# sche.net
KiCad netlist of a schematic drawn in EasyEDA
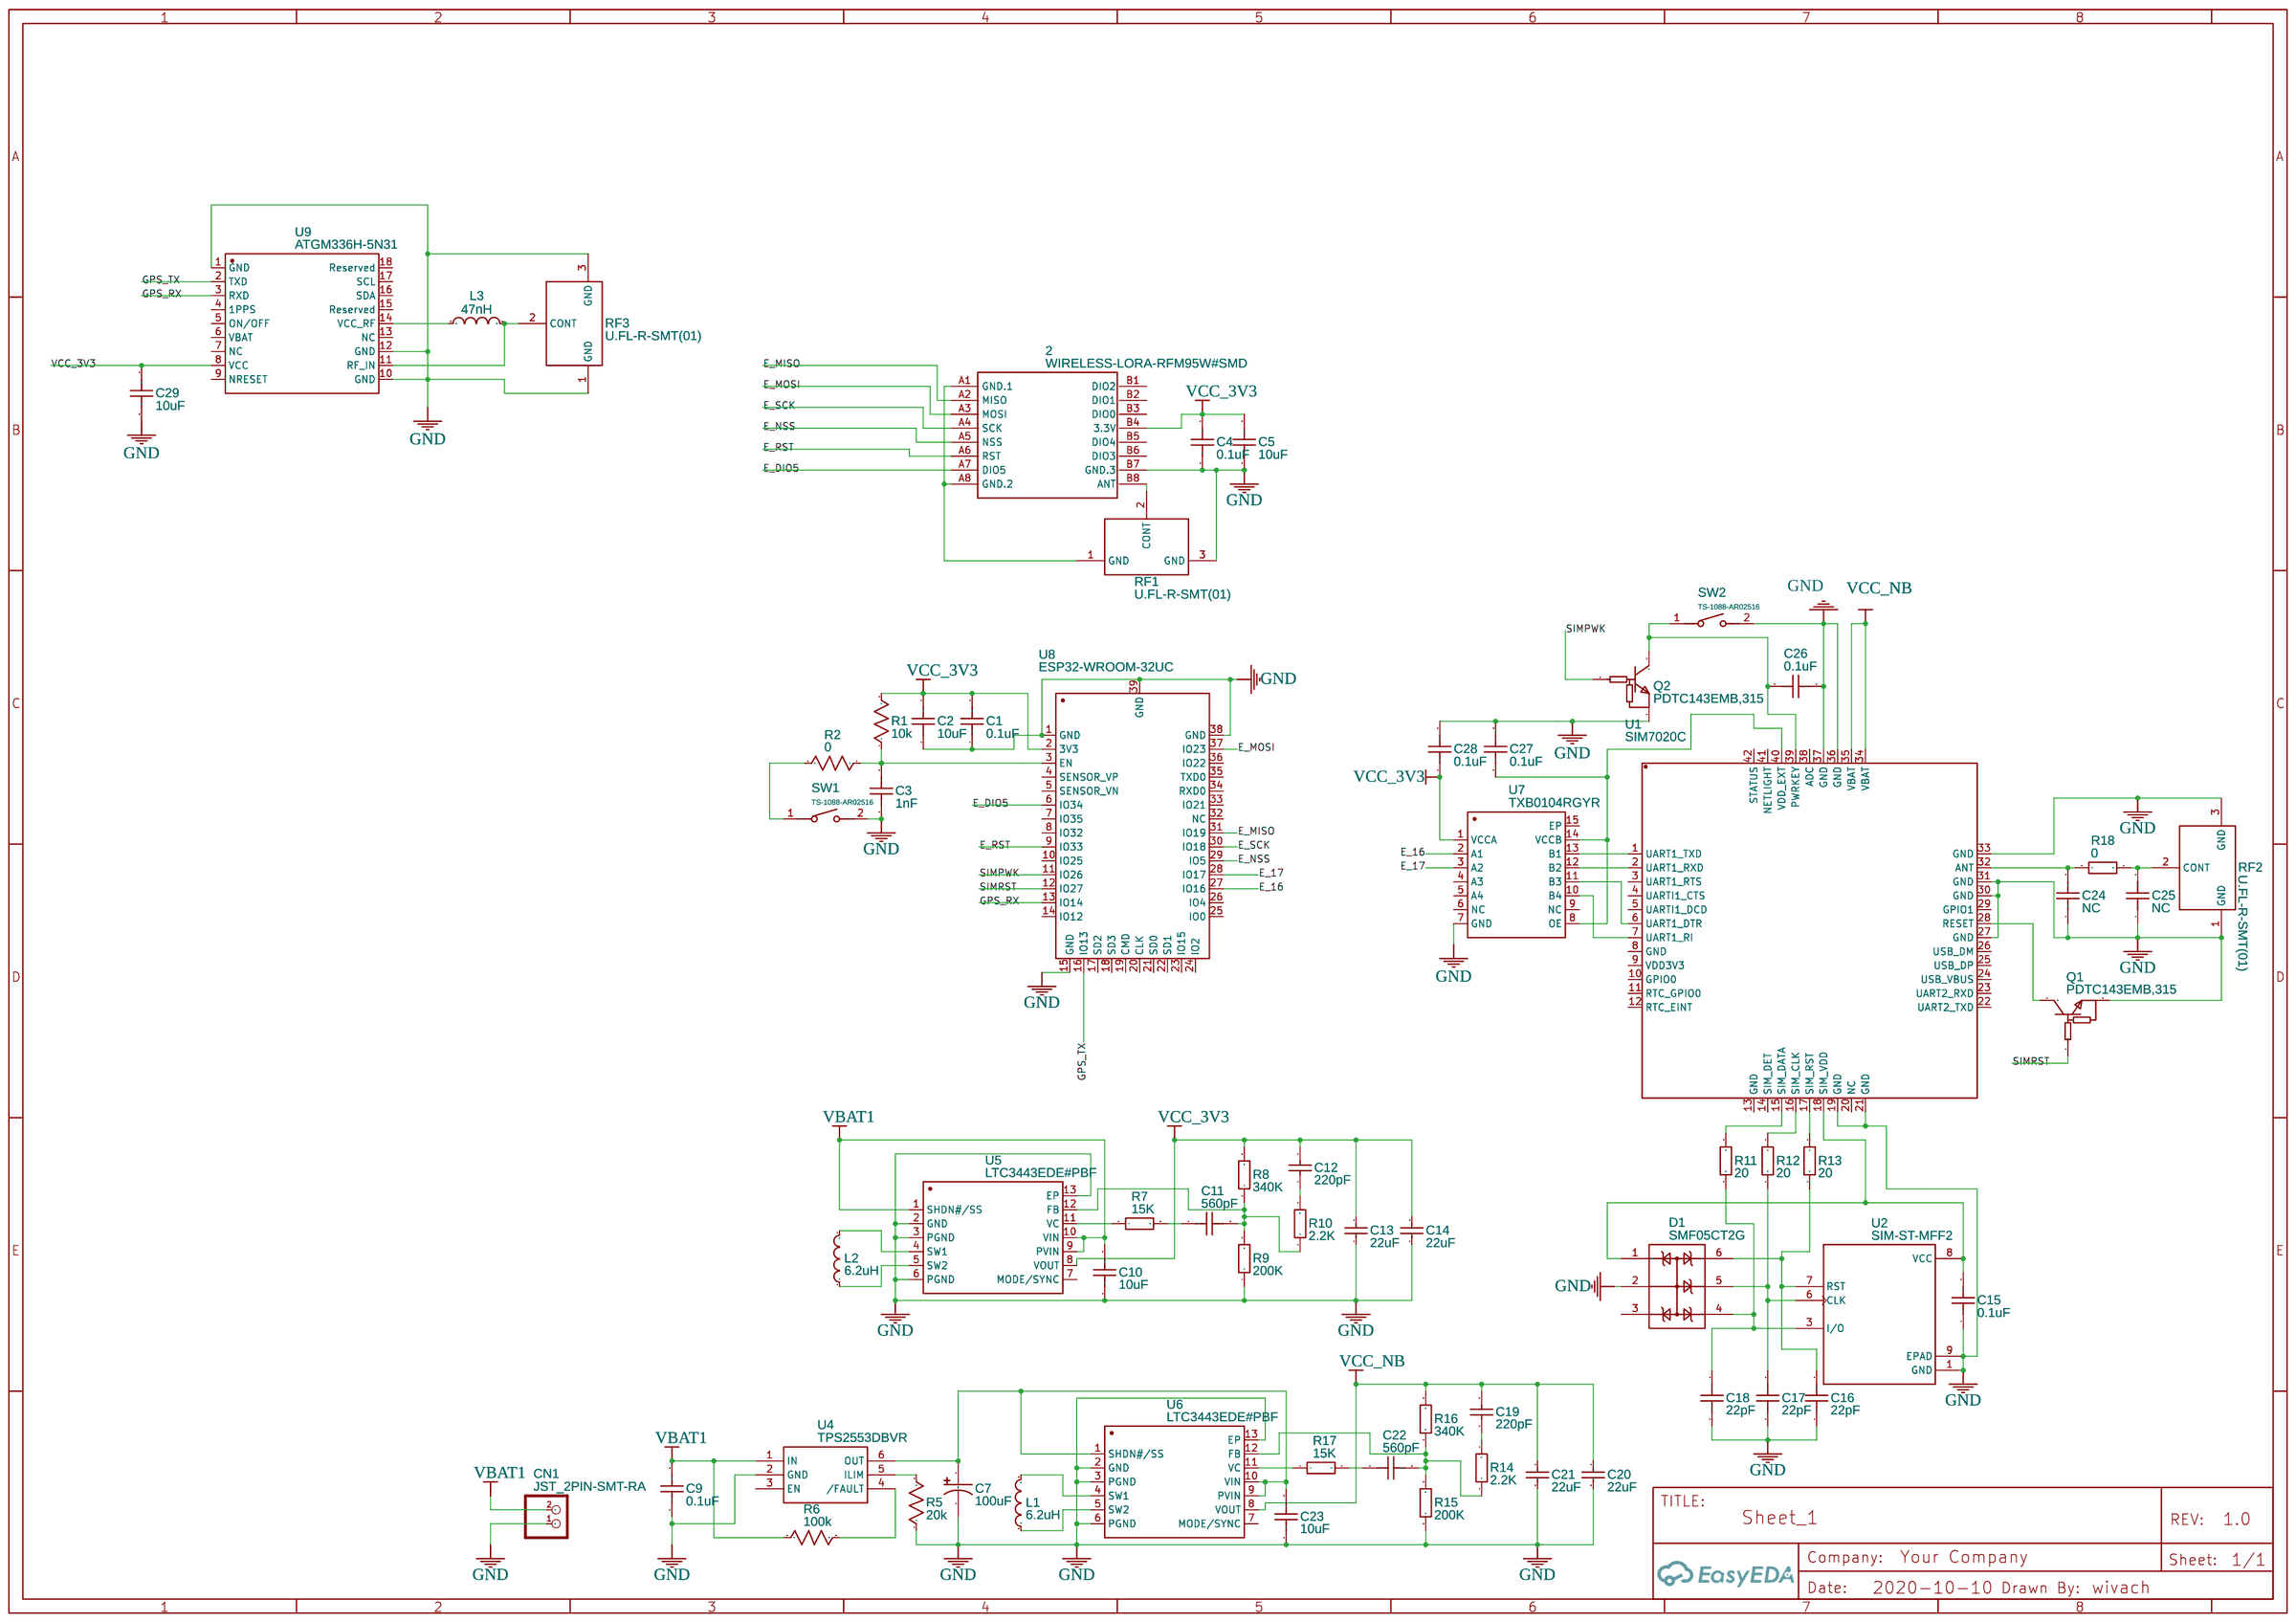
[diagram p0: schematic sheet]

(export (version "E")
  (design (tool "Eeschema 10.0.6"))
  (components
    (comp (ref "2") (value "WIRELESS-LORA-RFM95W#SMD") (libsource (lib "") (part "WIRELESS-LORA-RFM95W#SMD")))
    (comp (ref "C1")
      (value "0.1uF")
      (fields
        (field (name "BOM_Manufacturer Part") "GRM188R71H104KA93D")
        (field (name "BOM_Supplier Part") "C77055")
      )
      (libsource (lib "") (part "C_0603_US"))
    )
    (comp (ref "C2")
      (value "10uF")
      (fields
        (field (name "BOM_Manufacturer Part") "GRM188R60J106ME47D")
        (field (name "BOM_Supplier Part") "C77041")
      )
      (libsource (lib "") (part "C_0603_US"))
    )
    (comp (ref "C3")
      (value "1nF")
      (fields
        (field (name "BOM_Manufacturer Part") "TCC0603X7R102K500CT")
        (field (name "BOM_Supplier Part") "C282515")
      )
      (libsource (lib "") (part "C_0603_US"))
    )
    (comp (ref "C4")
      (value "0.1uF")
      (fields
        (field (name "BOM_Manufacturer Part") "GRM188R71H104KA93D")
        (field (name "BOM_Supplier Part") "C77055")
      )
      (libsource (lib "") (part "C_0603_US"))
    )
    (comp (ref "C5")
      (value "10uF")
      (fields
        (field (name "BOM_Manufacturer Part") "GRM188R60J106ME47D")
        (field (name "BOM_Supplier Part") "C77041")
      )
      (libsource (lib "") (part "C_0603_US"))
    )
    (comp (ref "C7")
      (value "100uF")
      (fields
        (field (name "BOM_Manufacturer Part") "TC212B107M010Y")
        (field (name "BOM_Supplier Part") "C110782")
      )
      (libsource (lib "") (part "TC212B107M010Y"))
    )
    (comp (ref "C9")
      (value "0.1uF")
      (fields
        (field (name "BOM_Manufacturer Part") "GRM188R71H104KA93D")
        (field (name "BOM_Supplier Part") "C77055")
      )
      (libsource (lib "") (part "C_0603_US"))
    )
    (comp (ref "C10")
      (value "10uF")
      (fields
        (field (name "BOM_Manufacturer Part") "C0805X5R106K160NT")
        (field (name "BOM_Supplier Part") "C466793")
      )
      (libsource (lib "") (part "C0805X5R106K160NT"))
    )
    (comp (ref "C11")
      (value "560pF")
      (fields
        (field (name "BOM_Manufacturer Part") "0603CG561J500NT")
        (field (name "BOM_Supplier Part") "C43962")
      )
      (libsource (lib "") (part "0603CG561J500NT"))
    )
    (comp (ref "C12")
      (value "220pF")
      (fields
        (field (name "BOM_Manufacturer Part") "CL10B221KB8NNNC")
        (field (name "BOM_Supplier Part") "C1603")
      )
      (libsource (lib "") (part "CL10B221KB8NNNC"))
    )
    (comp (ref "C13")
      (value "22uF")
      (fields
        (field (name "BOM_Manufacturer Part") "JMK316ABJ226KL-T")
        (field (name "BOM_Supplier Part") "C478848")
      )
      (libsource (lib "") (part "JMK316ABJ226KL-T"))
    )
    (comp (ref "C14")
      (value "22uF")
      (fields
        (field (name "BOM_Manufacturer Part") "JMK316ABJ226KL-T")
        (field (name "BOM_Supplier Part") "C478848")
      )
      (libsource (lib "") (part "JMK316ABJ226KL-T"))
    )
    (comp (ref "C15")
      (value "0.1uF")
      (fields
        (field (name "BOM_Manufacturer Part") "GRM188R71H104KA93D")
        (field (name "BOM_Supplier Part") "C77055")
      )
      (libsource (lib "") (part "C_0603_US"))
    )
    (comp (ref "C16")
      (value "22pF")
      (fields
        (field (name "BOM_Manufacturer Part") "CC0603GRNPO9BN220")
        (field (name "BOM_Supplier Part") "C327276")
      )
      (libsource (lib "") (part "CC0603GRNPO9BN220"))
    )
    (comp (ref "C17")
      (value "22pF")
      (fields
        (field (name "BOM_Manufacturer Part") "CC0603GRNPO9BN220")
        (field (name "BOM_Supplier Part") "C327276")
      )
      (libsource (lib "") (part "CC0603GRNPO9BN220"))
    )
    (comp (ref "C18")
      (value "22pF")
      (fields
        (field (name "BOM_Manufacturer Part") "CC0603GRNPO9BN220")
        (field (name "BOM_Supplier Part") "C327276")
      )
      (libsource (lib "") (part "CC0603GRNPO9BN220"))
    )
    (comp (ref "C19")
      (value "220pF")
      (fields
        (field (name "BOM_Manufacturer Part") "CL10B221KB8NNNC")
        (field (name "BOM_Supplier Part") "C1603")
      )
      (libsource (lib "") (part "CL10B221KB8NNNC"))
    )
    (comp (ref "C20")
      (value "22uF")
      (fields
        (field (name "BOM_Manufacturer Part") "JMK316ABJ226KL-T")
        (field (name "BOM_Supplier Part") "C478848")
      )
      (libsource (lib "") (part "JMK316ABJ226KL-T"))
    )
    (comp (ref "C21")
      (value "22uF")
      (fields
        (field (name "BOM_Manufacturer Part") "JMK316ABJ226KL-T")
        (field (name "BOM_Supplier Part") "C478848")
      )
      (libsource (lib "") (part "JMK316ABJ226KL-T"))
    )
    (comp (ref "C22")
      (value "560pF")
      (fields
        (field (name "BOM_Manufacturer Part") "0603CG561J500NT")
        (field (name "BOM_Supplier Part") "C43962")
      )
      (libsource (lib "") (part "0603CG561J500NT"))
    )
    (comp (ref "C23")
      (value "10uF")
      (fields
        (field (name "BOM_Manufacturer Part") "C0805X5R106K160NT")
        (field (name "BOM_Supplier Part") "C466793")
      )
      (libsource (lib "") (part "C0805X5R106K160NT"))
    )
    (comp (ref "C24") (value "NC") (libsource (lib "") (part "C_0603_US")))
    (comp (ref "C25") (value "NC") (libsource (lib "") (part "C_0603_US")))
    (comp (ref "C26")
      (value "0.1uF")
      (fields
        (field (name "BOM_Manufacturer Part") "GRM188R71H104KA93D")
        (field (name "BOM_Supplier Part") "C77055")
      )
      (libsource (lib "") (part "C_0603_US_1"))
    )
    (comp (ref "C27")
      (value "0.1uF")
      (fields
        (field (name "BOM_Manufacturer Part") "GRM188R71H104KA93D")
        (field (name "BOM_Supplier Part") "C77055")
      )
      (libsource (lib "") (part "C_0603_US"))
    )
    (comp (ref "C28")
      (value "0.1uF")
      (fields
        (field (name "BOM_Manufacturer Part") "GRM188R71H104KA93D")
        (field (name "BOM_Supplier Part") "C77055")
      )
      (libsource (lib "") (part "C_0603_US"))
    )
    (comp (ref "C29")
      (value "10uF")
      (fields
        (field (name "BOM_Manufacturer Part") "GRM188R60J106ME47D")
        (field (name "BOM_Supplier Part") "C77041")
      )
      (libsource (lib "") (part "C_0603_US"))
    )
    (comp (ref "CN1")
      (value "JST_2PIN-SMT-RA")
      (fields
        (field (name "BOM_Manufacturer Part") "S2B-PH-SM4-TB(LF)(SN)")
        (field (name "BOM_Supplier Part") "C295747")
      )
      (libsource (lib "") (part "JST_2PIN-SMT-RA"))
    )
    (comp (ref "D1")
      (value "SMF05CT2G")
      (fields (field (name "BOM_Supplier Part") "C513065"))
      (libsource (lib "") (part "SMF05CT2G"))
    )
    (comp (ref "L1")
      (value "6.2uH")
      (fields
        (field (name "BOM_Manufacturer Part") "CDRH5D28NP-6R2NC")
        (field (name "BOM_Supplier Part") "C312979")
      )
      (libsource (lib "") (part "CDRH5D28NP-6R2NC"))
    )
    (comp (ref "L2")
      (value "6.2uH")
      (fields
        (field (name "BOM_Manufacturer Part") "CDRH5D28NP-6R2NC")
        (field (name "BOM_Supplier Part") "C312979")
      )
      (libsource (lib "") (part "CDRH5D28NP-6R2NC_2"))
    )
    (comp (ref "L3")
      (value "47nH")
      (fields
        (field (name "BOM_Manufacturer Part") "CDRH5D28NP-6R2NC")
        (field (name "BOM_Supplier Part") "C312979")
      )
      (libsource (lib "") (part "CDRH5D28NP-6R2NC_1"))
    )
    (comp (ref "Q1")
      (value "PDTC143EMB,315")
      (fields (field (name "BOM_Supplier Part") "C552203"))
      (libsource (lib "") (part "PDTC143EMB,315_1"))
    )
    (comp (ref "Q2")
      (value "PDTC143EMB,315")
      (fields (field (name "BOM_Supplier Part") "C552203"))
      (libsource (lib "") (part "PDTC143EMB,315"))
    )
    (comp (ref "R1")
      (value "10k")
      (fields
        (field (name "BOM_Manufacturer Part") "RCT0310KJLF")
        (field (name "BOM_Supplier Part") "C177337")
      )
      (libsource (lib "") (part "R_0603_US"))
    )
    (comp (ref "R2")
      (value "0")
      (fields
        (field (name "BOM_Manufacturer Part") "0603WAF0000T5E")
        (field (name "BOM_Supplier Part") "C21189")
      )
      (libsource (lib "") (part "R_0603_US_1"))
    )
    (comp (ref "R5")
      (value "20k")
      (fields
        (field (name "BOM_Manufacturer Part") "SR06X203JTL")
        (field (name "BOM_Supplier Part") "C305157")
      )
      (libsource (lib "") (part "R_0603_US"))
    )
    (comp (ref "R6")
      (value "100k")
      (fields
        (field (name "BOM_Manufacturer Part") "RC0201JR-07100KL")
        (field (name "BOM_Supplier Part") "C106230")
      )
      (libsource (lib "") (part "R_0603_US_2"))
    )
    (comp (ref "R7")
      (value "15K")
      (fields
        (field (name "BOM_Manufacturer Part") "ETCR0603F15K0K9")
        (field (name "BOM_Supplier Part") "C365386")
      )
      (libsource (lib "") (part "ETCR0603F15K0K9"))
    )
    (comp (ref "R8")
      (value "340K")
      (fields
        (field (name "BOM_Manufacturer Part") "AC0603FR-07340KL")
        (field (name "BOM_Supplier Part") "C227826")
      )
      (libsource (lib "") (part "AC0603FR-07340KL"))
    )
    (comp (ref "R9")
      (value "200K")
      (fields
        (field (name "BOM_Manufacturer Part") "AF0603FR-07200KL")
        (field (name "BOM_Supplier Part") "C144091")
      )
      (libsource (lib "") (part "AF0603FR-07200KL"))
    )
    (comp (ref "R10")
      (value "2.2K")
      (fields
        (field (name "BOM_Manufacturer Part") "RMC06032.2K5%N")
        (field (name "BOM_Supplier Part") "C325643")
      )
      (libsource (lib "") (part "RMC06032.2K5%N"))
    )
    (comp (ref "R11")
      (value "20")
      (fields
        (field (name "BOM_Manufacturer Part") "ERJUP3F20R0V")
        (field (name "BOM_Supplier Part") "C544033")
      )
      (libsource (lib "") (part "ERJUP3F20R0V"))
    )
    (comp (ref "R12")
      (value "20")
      (fields
        (field (name "BOM_Manufacturer Part") "ERJUP3F20R0V")
        (field (name "BOM_Supplier Part") "C544033")
      )
      (libsource (lib "") (part "ERJUP3F20R0V"))
    )
    (comp (ref "R13")
      (value "20")
      (fields
        (field (name "BOM_Manufacturer Part") "ERJUP3F20R0V")
        (field (name "BOM_Supplier Part") "C544033")
      )
      (libsource (lib "") (part "ERJUP3F20R0V"))
    )
    (comp (ref "R14")
      (value "2.2K")
      (fields
        (field (name "BOM_Manufacturer Part") "RMC06032.2K5%N")
        (field (name "BOM_Supplier Part") "C325643")
      )
      (libsource (lib "") (part "RMC06032.2K5%N"))
    )
    (comp (ref "R15")
      (value "200K")
      (fields
        (field (name "BOM_Manufacturer Part") "AF0603FR-07200KL")
        (field (name "BOM_Supplier Part") "C144091")
      )
      (libsource (lib "") (part "AF0603FR-07200KL"))
    )
    (comp (ref "R16")
      (value "340K")
      (fields
        (field (name "BOM_Manufacturer Part") "AC0603FR-07340KL")
        (field (name "BOM_Supplier Part") "C227826")
      )
      (libsource (lib "") (part "AC0603FR-07340KL"))
    )
    (comp (ref "R17")
      (value "15K")
      (fields
        (field (name "BOM_Manufacturer Part") "ETCR0603F15K0K9")
        (field (name "BOM_Supplier Part") "C365386")
      )
      (libsource (lib "") (part "ETCR0603F15K0K9"))
    )
    (comp (ref "R18")
      (value "0")
      (fields
        (field (name "BOM_Manufacturer Part") "ERJUP3F20R0V")
        (field (name "BOM_Supplier Part") "C544033")
      )
      (libsource (lib "") (part "ERJUP3F20R0V_1"))
    )
    (comp (ref "RF1")
      (value "U.FL-R-SMT(01)")
      (fields (field (name "BOM_Supplier Part") "C434812"))
      (libsource (lib "") (part "U.FL-R-SMT(01)_1"))
    )
    (comp (ref "RF2")
      (value "U.FL-R-SMT(01)")
      (fields (field (name "BOM_Supplier Part") "C434812"))
      (libsource (lib "") (part "U.FL-R-SMT(01)"))
    )
    (comp (ref "RF3")
      (value "U.FL-R-SMT(01)")
      (fields (field (name "BOM_Supplier Part") "C434812"))
      (libsource (lib "") (part "U.FL-R-SMT(01)"))
    )
    (comp (ref "SW1")
      (value "TS-1088-AR02516")
      (fields (field (name "BOM_Supplier Part") "C720478"))
      (libsource (lib "") (part "TS-1088-AR02516"))
    )
    (comp (ref "SW2")
      (value "TS-1088-AR02516")
      (fields (field (name "BOM_Supplier Part") "C720478"))
      (libsource (lib "") (part "TS-1088-AR02516"))
    )
    (comp (ref "U1")
      (value "SIM7020C")
      (fields (field (name "BOM_Supplier Part") "C188351"))
      (libsource (lib "") (part "SIM7020C"))
    )
    (comp (ref "U2") (value "SIM-ST-MFF2") (libsource (lib "") (part "SIM-ST-MFF2")))
    (comp (ref "U4")
      (value "TPS2553DBVR")
      (fields (field (name "BOM_Supplier Part") "C55266"))
      (libsource (lib "") (part "TPS2553DBVR"))
    )
    (comp (ref "U5")
      (value "LTC3443EDE#PBF")
      (fields (field (name "BOM_Supplier Part") "C684784"))
      (libsource (lib "") (part "LTC3443EDE#PBF"))
    )
    (comp (ref "U6")
      (value "LTC3443EDE#PBF")
      (fields (field (name "BOM_Supplier Part") "C684784"))
      (libsource (lib "") (part "LTC3443EDE#PBF"))
    )
    (comp (ref "U7")
      (value "TXB0104RGYR")
      (fields (field (name "BOM_Supplier Part") "C400708"))
      (libsource (lib "") (part "TXB0104RGYR"))
    )
    (comp (ref "U8")
      (value "ESP32-WROOM-32UC")
      (fields (field (name "BOM_Supplier Part") "C473014"))
      (libsource (lib "") (part "ESP32-WROOM-32UC"))
    )
    (comp (ref "U9")
      (value "ATGM336H-5N31")
      (fields (field (name "BOM_Supplier Part") "C90770"))
      (libsource (lib "") (part "ATGM336H-5N31"))
    )
  )
  (nets
    (net (code "1") (name "/E_16") (class "Default")
      (node (ref "U7") (pin "2") (pinfunction "A1_2") (pintype "unspecified"))
      (node (ref "U8") (pin "27") (pinfunction "IO16_27") (pintype "unspecified"))
    )
    (net (code "2") (name "/E_17") (class "Default")
      (node (ref "U7") (pin "3") (pinfunction "A2_3") (pintype "unspecified"))
      (node (ref "U8") (pin "28") (pinfunction "IO17_28") (pintype "unspecified"))
    )
    (net (code "3") (name "/E_DIO5") (class "Default")
      (node (ref "2") (pin "A7") (pinfunction "DIO5_A7") (pintype "bidirectional"))
      (node (ref "U8") (pin "6") (pinfunction "IO34_6") (pintype "unspecified"))
    )
    (net (code "4") (name "/E_MISO") (class "Default")
      (node (ref "2") (pin "A2") (pinfunction "MISO_A2") (pintype "bidirectional"))
      (node (ref "U8") (pin "31") (pinfunction "IO19_31") (pintype "unspecified"))
    )
    (net (code "5") (name "/E_MOSI") (class "Default")
      (node (ref "2") (pin "A3") (pinfunction "MOSI_A3") (pintype "bidirectional"))
      (node (ref "U8") (pin "37") (pinfunction "IO23_37") (pintype "unspecified"))
    )
    (net (code "6") (name "/E_NSS") (class "Default")
      (node (ref "2") (pin "A5") (pinfunction "NSS_A5") (pintype "bidirectional"))
      (node (ref "U8") (pin "29") (pinfunction "IO5_29") (pintype "unspecified"))
    )
    (net (code "7") (name "/E_RST") (class "Default")
      (node (ref "2") (pin "A6") (pinfunction "RST_A6") (pintype "bidirectional"))
      (node (ref "U8") (pin "9") (pinfunction "IO33_9") (pintype "unspecified"))
    )
    (net (code "8") (name "/E_SCK") (class "Default")
      (node (ref "2") (pin "A4") (pinfunction "SCK_A4") (pintype "bidirectional"))
      (node (ref "U8") (pin "30") (pinfunction "IO18_30") (pintype "unspecified"))
    )
    (net (code "9") (name "/GPS_RX") (class "Default")
      (node (ref "U8") (pin "13") (pinfunction "IO14_13") (pintype "unspecified"))
      (node (ref "U9") (pin "3") (pinfunction "RXD_3") (pintype "unspecified"))
    )
    (net (code "10") (name "/GPS_TX") (class "Default")
      (node (ref "U8") (pin "16") (pinfunction "IO13_16") (pintype "unspecified"))
      (node (ref "U9") (pin "2") (pinfunction "TXD_2") (pintype "unspecified"))
    )
    (net (code "11") (name "/SIMPWK") (class "Default")
      (node (ref "Q2") (pin "1") (pinfunction "B_1") (pintype "unspecified"))
      (node (ref "U8") (pin "11") (pinfunction "IO26_11") (pintype "unspecified"))
    )
    (net (code "12") (name "/SIMRST") (class "Default")
      (node (ref "Q1") (pin "1") (pinfunction "B_1") (pintype "unspecified"))
      (node (ref "U8") (pin "12") (pinfunction "IO27_12") (pintype "unspecified"))
    )
    (net (code "13") (name "GND") (class "Default")
      (node (ref "2") (pin "B7") (pinfunction "GND.3_B7") (pintype "bidirectional"))
      (node (ref "C1") (pin "1") (pinfunction "1_1") (pintype "unspecified"))
      (node (ref "C10") (pin "1") (pinfunction "1_1") (pintype "unspecified"))
      (node (ref "C13") (pin "1") (pinfunction "1_1") (pintype "input"))
      (node (ref "C14") (pin "1") (pinfunction "1_1") (pintype "input"))
      (node (ref "C15") (pin "1") (pinfunction "1_1") (pintype "unspecified"))
      (node (ref "C16") (pin "1") (pinfunction "1_1") (pintype "unspecified"))
      (node (ref "C17") (pin "1") (pinfunction "1_1") (pintype "unspecified"))
      (node (ref "C18") (pin "1") (pinfunction "1_1") (pintype "unspecified"))
      (node (ref "C2") (pin "1") (pinfunction "1_1") (pintype "unspecified"))
      (node (ref "C20") (pin "1") (pinfunction "1_1") (pintype "input"))
      (node (ref "C21") (pin "1") (pinfunction "1_1") (pintype "input"))
      (node (ref "C23") (pin "1") (pinfunction "1_1") (pintype "unspecified"))
      (node (ref "C24") (pin "1") (pinfunction "1_1") (pintype "unspecified"))
      (node (ref "C25") (pin "1") (pinfunction "1_1") (pintype "unspecified"))
      (node (ref "C26") (pin "1") (pinfunction "1_1") (pintype "unspecified"))
      (node (ref "C27") (pin "2") (pinfunction "2_2") (pintype "unspecified"))
      (node (ref "C28") (pin "2") (pinfunction "2_2") (pintype "unspecified"))
      (node (ref "C29") (pin "1") (pinfunction "1_1") (pintype "unspecified"))
      (node (ref "C3") (pin "1") (pinfunction "1_1") (pintype "unspecified"))
      (node (ref "C4") (pin "1") (pinfunction "1_1") (pintype "unspecified"))
      (node (ref "C5") (pin "1") (pinfunction "1_1") (pintype "unspecified"))
      (node (ref "C7") (pin "2") (pinfunction "2_2") (pintype "unspecified"))
      (node (ref "C9") (pin "1") (pinfunction "1_1") (pintype "unspecified"))
      (node (ref "CN1") (pin "1") (pinfunction "2_1") (pintype "unspecified"))
      (node (ref "D1") (pin "2") (pinfunction "A_2") (pintype "unspecified"))
      (node (ref "Q1") (pin "2") (pinfunction "E_2") (pintype "unspecified"))
      (node (ref "Q2") (pin "2") (pinfunction "E_2") (pintype "unspecified"))
      (node (ref "R15") (pin "1") (pinfunction "1_1") (pintype "unspecified"))
      (node (ref "R5") (pin "1") (pinfunction "1_1") (pintype "unspecified"))
      (node (ref "R9") (pin "1") (pinfunction "1_1") (pintype "unspecified"))
      (node (ref "RF1") (pin "3") (pinfunction "GND_3") (pintype "unspecified"))
      (node (ref "RF2") (pin "1") (pinfunction "GND_1") (pintype "unspecified"))
      (node (ref "RF2") (pin "3") (pinfunction "GND_3") (pintype "unspecified"))
      (node (ref "RF3") (pin "1") (pinfunction "GND_1") (pintype "unspecified"))
      (node (ref "RF3") (pin "3") (pinfunction "GND_3") (pintype "unspecified"))
      (node (ref "SW1") (pin "2") (pinfunction "2_2") (pintype "unspecified"))
      (node (ref "SW2") (pin "2") (pinfunction "2_2") (pintype "unspecified"))
      (node (ref "U1") (pin "19") (pinfunction "GND_19") (pintype "unspecified"))
      (node (ref "U1") (pin "21") (pinfunction "GND_21") (pintype "unspecified"))
      (node (ref "U1") (pin "27") (pinfunction "GND_27") (pintype "unspecified"))
      (node (ref "U1") (pin "30") (pinfunction "GND_30") (pintype "unspecified"))
      (node (ref "U1") (pin "31") (pinfunction "GND_31") (pintype "unspecified"))
      (node (ref "U1") (pin "33") (pinfunction "GND_33") (pintype "unspecified"))
      (node (ref "U1") (pin "36") (pinfunction "GND_36") (pintype "unspecified"))
      (node (ref "U1") (pin "37") (pinfunction "GND_37") (pintype "unspecified"))
      (node (ref "U2") (pin "1") (pinfunction "GND_1") (pintype "bidirectional"))
      (node (ref "U2") (pin "9") (pinfunction "EPAD_9") (pintype "bidirectional"))
      (node (ref "U4") (pin "2") (pinfunction "GND_2") (pintype "unspecified"))
      (node (ref "U5") (pin "13") (pinfunction "EP_13") (pintype "unspecified"))
      (node (ref "U5") (pin "2") (pinfunction "GND_2") (pintype "unspecified"))
      (node (ref "U5") (pin "3") (pinfunction "PGND_3") (pintype "unspecified"))
      (node (ref "U5") (pin "6") (pinfunction "PGND_6") (pintype "unspecified"))
      (node (ref "U6") (pin "13") (pinfunction "EP_13") (pintype "unspecified"))
      (node (ref "U6") (pin "2") (pinfunction "GND_2") (pintype "unspecified"))
      (node (ref "U6") (pin "3") (pinfunction "PGND_3") (pintype "unspecified"))
      (node (ref "U6") (pin "6") (pinfunction "PGND_6") (pintype "unspecified"))
      (node (ref "U7") (pin "7") (pinfunction "GND_7") (pintype "unspecified"))
      (node (ref "U8") (pin "1") (pinfunction "GND_1") (pintype "unspecified"))
      (node (ref "U8") (pin "15") (pinfunction "GND_15") (pintype "unspecified"))
      (node (ref "U8") (pin "38") (pinfunction "GND_38") (pintype "unspecified"))
      (node (ref "U8") (pin "39") (pinfunction "GND_39") (pintype "unspecified"))
      (node (ref "U9") (pin "1") (pinfunction "GND_1") (pintype "unspecified"))
      (node (ref "U9") (pin "10") (pinfunction "GND_10") (pintype "unspecified"))
      (node (ref "U9") (pin "12") (pinfunction "GND_12") (pintype "unspecified"))
    )
    (net (code "14") (name "Net-(2-ANT)") (class "Default")
      (node (ref "2") (pin "B8") (pinfunction "ANT_B8") (pintype "bidirectional"))
      (node (ref "RF1") (pin "2") (pinfunction "CONT_2") (pintype "unspecified"))
    )
    (net (code "15") (name "Net-(2-GND.1)") (class "Default")
      (node (ref "2") (pin "A1") (pinfunction "GND.1_A1") (pintype "bidirectional"))
      (node (ref "2") (pin "A8") (pinfunction "GND.2_A8") (pintype "bidirectional"))
      (node (ref "RF1") (pin "1") (pinfunction "GND_1") (pintype "unspecified"))
    )
    (net (code "16") (name "Net-(C11-Pad1)") (class "Default")
      (node (ref "C11") (pin "1") (pinfunction "1_1") (pintype "unspecified"))
      (node (ref "R7") (pin "2") (pinfunction "2_2") (pintype "unspecified"))
    )
    (net (code "17") (name "Net-(C12-Pad1)") (class "Default")
      (node (ref "C12") (pin "1") (pinfunction "1_1") (pintype "input"))
      (node (ref "R10") (pin "2") (pinfunction "2_2") (pintype "unspecified"))
    )
    (net (code "18") (name "Net-(C19-Pad1)") (class "Default")
      (node (ref "C19") (pin "1") (pinfunction "1_1") (pintype "input"))
      (node (ref "R14") (pin "2") (pinfunction "2_2") (pintype "unspecified"))
    )
    (net (code "19") (name "Net-(C22-Pad1)") (class "Default")
      (node (ref "C22") (pin "1") (pinfunction "1_1") (pintype "unspecified"))
      (node (ref "R17") (pin "2") (pinfunction "2_2") (pintype "unspecified"))
    )
    (net (code "20") (name "Net-(D1-C1)") (class "Default")
      (node (ref "C15") (pin "2") (pinfunction "2_2") (pintype "unspecified"))
      (node (ref "D1") (pin "1") (pinfunction "C1_1") (pintype "unspecified"))
      (node (ref "U1") (pin "18") (pinfunction "SIM_VDD_18") (pintype "unspecified"))
      (node (ref "U2") (pin "8") (pinfunction "VCC_8") (pintype "bidirectional"))
    )
    (net (code "21") (name "Net-(D1-C3)") (class "Default")
      (node (ref "C18") (pin "2") (pinfunction "2_2") (pintype "unspecified"))
      (node (ref "D1") (pin "4") (pinfunction "C3_4") (pintype "unspecified"))
      (node (ref "R11") (pin "1") (pinfunction "1_1") (pintype "unspecified"))
      (node (ref "U2") (pin "3") (pinfunction "I/O_3") (pintype "bidirectional"))
    )
    (net (code "22") (name "Net-(D1-C4)") (class "Default")
      (node (ref "C17") (pin "2") (pinfunction "2_2") (pintype "unspecified"))
      (node (ref "D1") (pin "5") (pinfunction "C4_5") (pintype "unspecified"))
      (node (ref "R12") (pin "1") (pinfunction "1_1") (pintype "unspecified"))
      (node (ref "U2") (pin "6") (pinfunction "CLK_6") (pintype "bidirectional"))
    )
    (net (code "23") (name "Net-(D1-C5)") (class "Default")
      (node (ref "C16") (pin "2") (pinfunction "2_2") (pintype "unspecified"))
      (node (ref "D1") (pin "6") (pinfunction "C5_6") (pintype "unspecified"))
      (node (ref "R13") (pin "1") (pinfunction "1_1") (pintype "unspecified"))
      (node (ref "U2") (pin "7") (pinfunction "RST_7") (pintype "bidirectional"))
    )
    (net (code "24") (name "Net-(Q1-C)") (class "Default")
      (node (ref "Q1") (pin "3") (pinfunction "C_3") (pintype "unspecified"))
      (node (ref "U1") (pin "28") (pinfunction "RESET_28") (pintype "unspecified"))
    )
    (net (code "25") (name "Net-(Q2-C)") (class "Default")
      (node (ref "C26") (pin "2") (pinfunction "2_2") (pintype "unspecified"))
      (node (ref "Q2") (pin "3") (pinfunction "C_3") (pintype "unspecified"))
      (node (ref "SW2") (pin "1") (pinfunction "1_1") (pintype "unspecified"))
      (node (ref "U1") (pin "39") (pinfunction "PWRKEY_39") (pintype "unspecified"))
    )
    (net (code "26") (name "Net-(R2-Pad2)") (class "Default")
      (node (ref "R2") (pin "2") (pinfunction "2_2") (pintype "unspecified"))
      (node (ref "SW1") (pin "1") (pinfunction "1_1") (pintype "unspecified"))
    )
    (net (code "27") (name "Net-(RF2-CONT)") (class "Default")
      (node (ref "C25") (pin "2") (pinfunction "2_2") (pintype "unspecified"))
      (node (ref "R18") (pin "1") (pinfunction "1_1") (pintype "unspecified"))
      (node (ref "RF2") (pin "2") (pinfunction "CONT_2") (pintype "unspecified"))
    )
    (net (code "28") (name "Net-(RF3-CONT)") (class "Default")
      (node (ref "L3") (pin "2") (pinfunction "2_2") (pintype "unspecified"))
      (node (ref "RF3") (pin "2") (pinfunction "CONT_2") (pintype "unspecified"))
      (node (ref "U9") (pin "11") (pinfunction "RF_IN_11") (pintype "unspecified"))
    )
    (net (code "29") (name "Net-(U1-ANT)") (class "Default")
      (node (ref "C24") (pin "2") (pinfunction "2_2") (pintype "unspecified"))
      (node (ref "R18") (pin "2") (pinfunction "2_2") (pintype "unspecified"))
      (node (ref "U1") (pin "32") (pinfunction "ANT_32") (pintype "unspecified"))
    )
    (net (code "30") (name "Net-(U1-SIM_CLK)") (class "Default")
      (node (ref "R12") (pin "2") (pinfunction "2_2") (pintype "unspecified"))
      (node (ref "U1") (pin "16") (pinfunction "SIM_CLK_16") (pintype "unspecified"))
    )
    (net (code "31") (name "Net-(U1-SIM_DATA)") (class "Default")
      (node (ref "R11") (pin "2") (pinfunction "2_2") (pintype "unspecified"))
      (node (ref "U1") (pin "15") (pinfunction "SIM_DATA_15") (pintype "unspecified"))
    )
    (net (code "32") (name "Net-(U1-SIM_RST)") (class "Default")
      (node (ref "R13") (pin "2") (pinfunction "2_2") (pintype "unspecified"))
      (node (ref "U1") (pin "17") (pinfunction "SIM_RST_17") (pintype "unspecified"))
    )
    (net (code "33") (name "Net-(U1-UART1_DTR)") (class "Default")
      (node (ref "U1") (pin "6") (pinfunction "UART1_DTR_6") (pintype "unspecified"))
      (node (ref "U7") (pin "11") (pinfunction "B3_11") (pintype "unspecified"))
    )
    (net (code "34") (name "Net-(U1-UART1_RI)") (class "Default")
      (node (ref "U1") (pin "7") (pinfunction "UART1_RI_7") (pintype "unspecified"))
      (node (ref "U7") (pin "10") (pinfunction "B4_10") (pintype "unspecified"))
    )
    (net (code "35") (name "Net-(U1-UART1_RXD)") (class "Default")
      (node (ref "U1") (pin "2") (pinfunction "UART1_RXD_2") (pintype "unspecified"))
      (node (ref "U7") (pin "12") (pinfunction "B2_12") (pintype "unspecified"))
    )
    (net (code "36") (name "Net-(U1-UART1_TXD)") (class "Default")
      (node (ref "U1") (pin "1") (pinfunction "UART1_TXD_1") (pintype "unspecified"))
      (node (ref "U7") (pin "13") (pinfunction "B1_13") (pintype "unspecified"))
    )
    (net (code "37") (name "Net-(U1-VDD_EXT)") (class "Default")
      (node (ref "C27") (pin "1") (pinfunction "1_1") (pintype "unspecified"))
      (node (ref "U1") (pin "40") (pinfunction "VDD_EXT_40") (pintype "unspecified"))
      (node (ref "U7") (pin "14") (pinfunction "VCCB_14") (pintype "unspecified"))
      (node (ref "U7") (pin "8") (pinfunction "OE_8") (pintype "unspecified"))
    )
    (net (code "38") (name "Net-(U4-ILIM)") (class "Default")
      (node (ref "R5") (pin "2") (pinfunction "2_2") (pintype "unspecified"))
      (node (ref "U4") (pin "5") (pinfunction "ILIM_5") (pintype "unspecified"))
    )
    (net (code "39") (name "Net-(U4-OUT)") (class "Default")
      (node (ref "C23") (pin "2") (pinfunction "2_2") (pintype "unspecified"))
      (node (ref "C7") (pin "1") (pinfunction "1_1") (pintype "unspecified"))
      (node (ref "U4") (pin "6") (pinfunction "OUT_6") (pintype "unspecified"))
      (node (ref "U6") (pin "1") (pinfunction "SHDN#/SS_1") (pintype "unspecified"))
      (node (ref "U6") (pin "10") (pinfunction "VIN_10") (pintype "unspecified"))
      (node (ref "U6") (pin "9") (pinfunction "PVIN_9") (pintype "unspecified"))
    )
    (net (code "40") (name "Net-(U4-{slash}FAULT)") (class "Default")
      (node (ref "R6") (pin "2") (pinfunction "2_2") (pintype "unspecified"))
      (node (ref "U4") (pin "4") (pinfunction "/FAULT_4") (pintype "unspecified"))
    )
    (net (code "41") (name "Net-(U5-FB)") (class "Default")
      (node (ref "C11") (pin "2") (pinfunction "2_2") (pintype "unspecified"))
      (node (ref "R10") (pin "1") (pinfunction "1_1") (pintype "unspecified"))
      (node (ref "R8") (pin "1") (pinfunction "1_1") (pintype "unspecified"))
      (node (ref "R9") (pin "2") (pinfunction "2_2") (pintype "unspecified"))
      (node (ref "U5") (pin "12") (pinfunction "FB_12") (pintype "unspecified"))
    )
    (net (code "42") (name "Net-(U5-SW1)") (class "Default")
      (node (ref "L2") (pin "2") (pinfunction "2_2") (pintype "unspecified"))
      (node (ref "U5") (pin "4") (pinfunction "SW1_4") (pintype "unspecified"))
    )
    (net (code "43") (name "Net-(U5-SW2)") (class "Default")
      (node (ref "L2") (pin "1") (pinfunction "1_1") (pintype "unspecified"))
      (node (ref "U5") (pin "5") (pinfunction "SW2_5") (pintype "unspecified"))
    )
    (net (code "44") (name "Net-(U5-VC)") (class "Default")
      (node (ref "R7") (pin "1") (pinfunction "1_1") (pintype "unspecified"))
      (node (ref "U5") (pin "11") (pinfunction "VC_11") (pintype "unspecified"))
    )
    (net (code "45") (name "Net-(U6-FB)") (class "Default")
      (node (ref "C22") (pin "2") (pinfunction "2_2") (pintype "unspecified"))
      (node (ref "R14") (pin "1") (pinfunction "1_1") (pintype "unspecified"))
      (node (ref "R15") (pin "2") (pinfunction "2_2") (pintype "unspecified"))
      (node (ref "R16") (pin "1") (pinfunction "1_1") (pintype "unspecified"))
      (node (ref "U6") (pin "12") (pinfunction "FB_12") (pintype "unspecified"))
    )
    (net (code "46") (name "Net-(U6-SW1)") (class "Default")
      (node (ref "L1") (pin "2") (pinfunction "2_2") (pintype "unspecified"))
      (node (ref "U6") (pin "4") (pinfunction "SW1_4") (pintype "unspecified"))
    )
    (net (code "47") (name "Net-(U6-SW2)") (class "Default")
      (node (ref "L1") (pin "1") (pinfunction "1_1") (pintype "unspecified"))
      (node (ref "U6") (pin "5") (pinfunction "SW2_5") (pintype "unspecified"))
    )
    (net (code "48") (name "Net-(U6-VC)") (class "Default")
      (node (ref "R17") (pin "1") (pinfunction "1_1") (pintype "unspecified"))
      (node (ref "U6") (pin "11") (pinfunction "VC_11") (pintype "unspecified"))
    )
    (net (code "49") (name "Net-(U8-EN)") (class "Default")
      (node (ref "C3") (pin "2") (pinfunction "2_2") (pintype "unspecified"))
      (node (ref "R1") (pin "1") (pinfunction "1_1") (pintype "unspecified"))
      (node (ref "R2") (pin "1") (pinfunction "1_1") (pintype "unspecified"))
      (node (ref "U8") (pin "3") (pinfunction "EN_3") (pintype "unspecified"))
    )
    (net (code "50") (name "Net-(U9-VCC_RF)") (class "Default")
      (node (ref "L3") (pin "1") (pinfunction "1_1") (pintype "unspecified"))
      (node (ref "U9") (pin "14") (pinfunction "VCC_RF_14") (pintype "unspecified"))
    )
    (net (code "51") (name "VBAT1") (class "Default")
      (node (ref "C10") (pin "2") (pinfunction "2_2") (pintype "unspecified"))
      (node (ref "C9") (pin "2") (pinfunction "2_2") (pintype "unspecified"))
      (node (ref "CN1") (pin "2") (pinfunction "1_2") (pintype "unspecified"))
      (node (ref "R6") (pin "1") (pinfunction "1_1") (pintype "unspecified"))
      (node (ref "U4") (pin "1") (pinfunction "IN_1") (pintype "unspecified"))
      (node (ref "U5") (pin "1") (pinfunction "SHDN#/SS_1") (pintype "unspecified"))
      (node (ref "U5") (pin "10") (pinfunction "VIN_10") (pintype "unspecified"))
      (node (ref "U5") (pin "9") (pinfunction "PVIN_9") (pintype "unspecified"))
    )
    (net (code "52") (name "VCC_3V3") (class "Default")
      (node (ref "2") (pin "B4") (pinfunction "3.3V_B4") (pintype "bidirectional"))
      (node (ref "C1") (pin "2") (pinfunction "2_2") (pintype "unspecified"))
      (node (ref "C12") (pin "2") (pinfunction "2_2") (pintype "input"))
      (node (ref "C13") (pin "2") (pinfunction "2_2") (pintype "input"))
      (node (ref "C14") (pin "2") (pinfunction "2_2") (pintype "input"))
      (node (ref "C2") (pin "2") (pinfunction "2_2") (pintype "unspecified"))
      (node (ref "C28") (pin "1") (pinfunction "1_1") (pintype "unspecified"))
      (node (ref "C29") (pin "2") (pinfunction "2_2") (pintype "unspecified"))
      (node (ref "C4") (pin "2") (pinfunction "2_2") (pintype "unspecified"))
      (node (ref "C5") (pin "2") (pinfunction "2_2") (pintype "unspecified"))
      (node (ref "R1") (pin "2") (pinfunction "2_2") (pintype "unspecified"))
      (node (ref "R8") (pin "2") (pinfunction "2_2") (pintype "unspecified"))
      (node (ref "U5") (pin "8") (pinfunction "VOUT_8") (pintype "unspecified"))
      (node (ref "U7") (pin "1") (pinfunction "VCCA_1") (pintype "unspecified"))
      (node (ref "U8") (pin "2") (pinfunction "3V3_2") (pintype "unspecified"))
      (node (ref "U9") (pin "8") (pinfunction "VCC_8") (pintype "unspecified"))
    )
    (net (code "53") (name "VCC_NB") (class "Default")
      (node (ref "C19") (pin "2") (pinfunction "2_2") (pintype "input"))
      (node (ref "C20") (pin "2") (pinfunction "2_2") (pintype "input"))
      (node (ref "C21") (pin "2") (pinfunction "2_2") (pintype "input"))
      (node (ref "R16") (pin "2") (pinfunction "2_2") (pintype "unspecified"))
      (node (ref "U1") (pin "34") (pinfunction "VBAT_34") (pintype "unspecified"))
      (node (ref "U1") (pin "35") (pinfunction "VBAT_35") (pintype "unspecified"))
      (node (ref "U6") (pin "8") (pinfunction "VOUT_8") (pintype "unspecified"))
    )
    (net (code "54") (name "unconnected-(2-DIO0-PadB3)") (class "Default")
      (node (ref "2") (pin "B3") (pinfunction "DIO0_B3") (pintype "bidirectional"))
    )
    (net (code "55") (name "unconnected-(2-DIO1-PadB2)") (class "Default")
      (node (ref "2") (pin "B2") (pinfunction "DIO1_B2") (pintype "bidirectional"))
    )
    (net (code "56") (name "unconnected-(2-DIO2-PadB1)") (class "Default")
      (node (ref "2") (pin "B1") (pinfunction "DIO2_B1") (pintype "bidirectional"))
    )
    (net (code "57") (name "unconnected-(2-DIO3-PadB6)") (class "Default")
      (node (ref "2") (pin "B6") (pinfunction "DIO3_B6") (pintype "bidirectional"))
    )
    (net (code "58") (name "unconnected-(2-DIO4-PadB5)") (class "Default")
      (node (ref "2") (pin "B5") (pinfunction "DIO4_B5") (pintype "bidirectional"))
    )
    (net (code "59") (name "unconnected-(D1-C2-Pad3)") (class "Default")
      (node (ref "D1") (pin "3") (pinfunction "C2_3") (pintype "unspecified"))
    )
    (net (code "60") (name "unconnected-(U1-ADC-Pad38)") (class "Default")
      (node (ref "U1") (pin "38") (pinfunction "ADC_38") (pintype "unspecified"))
    )
    (net (code "61") (name "unconnected-(U1-GND-Pad8)") (class "Default")
      (node (ref "U1") (pin "8") (pinfunction "GND_8") (pintype "unspecified"))
    )
    (net (code "62") (name "unconnected-(U1-GND-Pad13)") (class "Default")
      (node (ref "U1") (pin "13") (pinfunction "GND_13") (pintype "unspecified"))
    )
    (net (code "63") (name "unconnected-(U1-GPIO0-Pad10)") (class "Default")
      (node (ref "U1") (pin "10") (pinfunction "GPIO0_10") (pintype "unspecified"))
    )
    (net (code "64") (name "unconnected-(U1-GPIO1-Pad29)") (class "Default")
      (node (ref "U1") (pin "29") (pinfunction "GPIO1_29") (pintype "unspecified"))
    )
    (net (code "65") (name "unconnected-(U1-NC-Pad20)") (class "Default")
      (node (ref "U1") (pin "20") (pinfunction "NC_20") (pintype "unspecified"))
    )
    (net (code "66") (name "unconnected-(U1-NETLIGHT-Pad41)") (class "Default")
      (node (ref "U1") (pin "41") (pinfunction "NETLIGHT_41") (pintype "unspecified"))
    )
    (net (code "67") (name "unconnected-(U1-RTC_EINT-Pad12)") (class "Default")
      (node (ref "U1") (pin "12") (pinfunction "RTC_EINT_12") (pintype "unspecified"))
    )
    (net (code "68") (name "unconnected-(U1-RTC_GPIO0-Pad11)") (class "Default")
      (node (ref "U1") (pin "11") (pinfunction "RTC_GPIO0_11") (pintype "unspecified"))
    )
    (net (code "69") (name "unconnected-(U1-SIM_DET-Pad14)") (class "Default")
      (node (ref "U1") (pin "14") (pinfunction "SIM_DET_14") (pintype "unspecified"))
    )
    (net (code "70") (name "unconnected-(U1-STATUS-Pad42)") (class "Default")
      (node (ref "U1") (pin "42") (pinfunction "STATUS_42") (pintype "unspecified"))
    )
    (net (code "71") (name "unconnected-(U1-UART1_RTS-Pad3)") (class "Default")
      (node (ref "U1") (pin "3") (pinfunction "UART1_RTS_3") (pintype "unspecified"))
    )
    (net (code "72") (name "unconnected-(U1-UART2_RXD-Pad23)") (class "Default")
      (node (ref "U1") (pin "23") (pinfunction "UART2_RXD_23") (pintype "unspecified"))
    )
    (net (code "73") (name "unconnected-(U1-UART2_TXD-Pad22)") (class "Default")
      (node (ref "U1") (pin "22") (pinfunction "UART2_TXD_22") (pintype "unspecified"))
    )
    (net (code "74") (name "unconnected-(U1-UARTI1_CTS-Pad4)") (class "Default")
      (node (ref "U1") (pin "4") (pinfunction "UARTI1_CTS_4") (pintype "unspecified"))
    )
    (net (code "75") (name "unconnected-(U1-UARTI1_DCD-Pad5)") (class "Default")
      (node (ref "U1") (pin "5") (pinfunction "UARTI1_DCD_5") (pintype "unspecified"))
    )
    (net (code "76") (name "unconnected-(U1-USB_DM-Pad26)") (class "Default")
      (node (ref "U1") (pin "26") (pinfunction "USB_DM_26") (pintype "unspecified"))
    )
    (net (code "77") (name "unconnected-(U1-USB_DP-Pad25)") (class "Default")
      (node (ref "U1") (pin "25") (pinfunction "USB_DP_25") (pintype "unspecified"))
    )
    (net (code "78") (name "unconnected-(U1-USB_VBUS-Pad24)") (class "Default")
      (node (ref "U1") (pin "24") (pinfunction "USB_VBUS_24") (pintype "unspecified"))
    )
    (net (code "79") (name "unconnected-(U1-VDD3V3-Pad9)") (class "Default")
      (node (ref "U1") (pin "9") (pinfunction "VDD3V3_9") (pintype "unspecified"))
    )
    (net (code "80") (name "unconnected-(U4-EN-Pad3)") (class "Default")
      (node (ref "U4") (pin "3") (pinfunction "EN_3") (pintype "unspecified"))
    )
    (net (code "81") (name "unconnected-(U5-MODE{slash}SYNC-Pad7)") (class "Default")
      (node (ref "U5") (pin "7") (pinfunction "MODE/SYNC_7") (pintype "unspecified"))
    )
    (net (code "82") (name "unconnected-(U6-MODE{slash}SYNC-Pad7)") (class "Default")
      (node (ref "U6") (pin "7") (pinfunction "MODE/SYNC_7") (pintype "unspecified"))
    )
    (net (code "83") (name "unconnected-(U7-A3-Pad4)") (class "Default")
      (node (ref "U7") (pin "4") (pinfunction "A3_4") (pintype "unspecified"))
    )
    (net (code "84") (name "unconnected-(U7-A4-Pad5)") (class "Default")
      (node (ref "U7") (pin "5") (pinfunction "A4_5") (pintype "unspecified"))
    )
    (net (code "85") (name "unconnected-(U7-EP-Pad15)") (class "Default")
      (node (ref "U7") (pin "15") (pinfunction "EP_15") (pintype "unspecified"))
    )
    (net (code "86") (name "unconnected-(U7-NC-Pad6)") (class "Default")
      (node (ref "U7") (pin "6") (pinfunction "NC_6") (pintype "unspecified"))
    )
    (net (code "87") (name "unconnected-(U7-NC-Pad9)") (class "Default")
      (node (ref "U7") (pin "9") (pinfunction "NC_9") (pintype "unspecified"))
    )
    (net (code "88") (name "unconnected-(U8-CLK-Pad20)") (class "Default")
      (node (ref "U8") (pin "20") (pinfunction "CLK_20") (pintype "unspecified"))
    )
    (net (code "89") (name "unconnected-(U8-CMD-Pad19)") (class "Default")
      (node (ref "U8") (pin "19") (pinfunction "CMD_19") (pintype "unspecified"))
    )
    (net (code "90") (name "unconnected-(U8-IO0-Pad25)") (class "Default")
      (node (ref "U8") (pin "25") (pinfunction "IO0_25") (pintype "unspecified"))
    )
    (net (code "91") (name "unconnected-(U8-IO2-Pad24)") (class "Default")
      (node (ref "U8") (pin "24") (pinfunction "IO2_24") (pintype "unspecified"))
    )
    (net (code "92") (name "unconnected-(U8-IO4-Pad26)") (class "Default")
      (node (ref "U8") (pin "26") (pinfunction "IO4_26") (pintype "unspecified"))
    )
    (net (code "93") (name "unconnected-(U8-IO12-Pad14)") (class "Default")
      (node (ref "U8") (pin "14") (pinfunction "IO12_14") (pintype "unspecified"))
    )
    (net (code "94") (name "unconnected-(U8-IO15-Pad23)") (class "Default")
      (node (ref "U8") (pin "23") (pinfunction "IO15_23") (pintype "unspecified"))
    )
    (net (code "95") (name "unconnected-(U8-IO21-Pad33)") (class "Default")
      (node (ref "U8") (pin "33") (pinfunction "IO21_33") (pintype "unspecified"))
    )
    (net (code "96") (name "unconnected-(U8-IO22-Pad36)") (class "Default")
      (node (ref "U8") (pin "36") (pinfunction "IO22_36") (pintype "unspecified"))
    )
    (net (code "97") (name "unconnected-(U8-IO25-Pad10)") (class "Default")
      (node (ref "U8") (pin "10") (pinfunction "IO25_10") (pintype "unspecified"))
    )
    (net (code "98") (name "unconnected-(U8-IO32-Pad8)") (class "Default")
      (node (ref "U8") (pin "8") (pinfunction "IO32_8") (pintype "unspecified"))
    )
    (net (code "99") (name "unconnected-(U8-IO35-Pad7)") (class "Default")
      (node (ref "U8") (pin "7") (pinfunction "IO35_7") (pintype "unspecified"))
    )
    (net (code "100") (name "unconnected-(U8-NC-Pad32)") (class "Default")
      (node (ref "U8") (pin "32") (pinfunction "NC_32") (pintype "unspecified"))
    )
    (net (code "101") (name "unconnected-(U8-RXD0-Pad34)") (class "Default")
      (node (ref "U8") (pin "34") (pinfunction "RXD0_34") (pintype "unspecified"))
    )
    (net (code "102") (name "unconnected-(U8-SD0-Pad21)") (class "Default")
      (node (ref "U8") (pin "21") (pinfunction "SD0_21") (pintype "unspecified"))
    )
    (net (code "103") (name "unconnected-(U8-SD1-Pad22)") (class "Default")
      (node (ref "U8") (pin "22") (pinfunction "SD1_22") (pintype "unspecified"))
    )
    (net (code "104") (name "unconnected-(U8-SD2-Pad17)") (class "Default")
      (node (ref "U8") (pin "17") (pinfunction "SD2_17") (pintype "unspecified"))
    )
    (net (code "105") (name "unconnected-(U8-SD3-Pad18)") (class "Default")
      (node (ref "U8") (pin "18") (pinfunction "SD3_18") (pintype "unspecified"))
    )
    (net (code "106") (name "unconnected-(U8-SENSOR_VN-Pad5)") (class "Default")
      (node (ref "U8") (pin "5") (pinfunction "SENSOR_VN_5") (pintype "unspecified"))
    )
    (net (code "107") (name "unconnected-(U8-SENSOR_VP-Pad4)") (class "Default")
      (node (ref "U8") (pin "4") (pinfunction "SENSOR_VP_4") (pintype "unspecified"))
    )
    (net (code "108") (name "unconnected-(U8-TXD0-Pad35)") (class "Default")
      (node (ref "U8") (pin "35") (pinfunction "TXD0_35") (pintype "unspecified"))
    )
    (net (code "109") (name "unconnected-(U9-1PPS-Pad4)") (class "Default")
      (node (ref "U9") (pin "4") (pinfunction "1PPS_4") (pintype "unspecified"))
    )
    (net (code "110") (name "unconnected-(U9-NC-Pad7)") (class "Default")
      (node (ref "U9") (pin "7") (pinfunction "NC_7") (pintype "unspecified"))
    )
    (net (code "111") (name "unconnected-(U9-NC-Pad13)") (class "Default")
      (node (ref "U9") (pin "13") (pinfunction "NC_13") (pintype "unspecified"))
    )
    (net (code "112") (name "unconnected-(U9-NRESET-Pad9)") (class "Default")
      (node (ref "U9") (pin "9") (pinfunction "NRESET_9") (pintype "unspecified"))
    )
    (net (code "113") (name "unconnected-(U9-ON{slash}OFF-Pad5)") (class "Default")
      (node (ref "U9") (pin "5") (pinfunction "ON/OFF_5") (pintype "unspecified"))
    )
    (net (code "114") (name "unconnected-(U9-Reserved-Pad15)") (class "Default")
      (node (ref "U9") (pin "15") (pinfunction "Reserved_15") (pintype "unspecified"))
    )
    (net (code "115") (name "unconnected-(U9-Reserved-Pad18)") (class "Default")
      (node (ref "U9") (pin "18") (pinfunction "Reserved_18") (pintype "unspecified"))
    )
    (net (code "116") (name "unconnected-(U9-SCL-Pad17)") (class "Default")
      (node (ref "U9") (pin "17") (pinfunction "SCL_17") (pintype "unspecified"))
    )
    (net (code "117") (name "unconnected-(U9-SDA-Pad16)") (class "Default")
      (node (ref "U9") (pin "16") (pinfunction "SDA_16") (pintype "unspecified"))
    )
    (net (code "118") (name "unconnected-(U9-VBAT-Pad6)") (class "Default")
      (node (ref "U9") (pin "6") (pinfunction "VBAT_6") (pintype "unspecified"))
    )
  )
)
